# openSX70-dongle-USB-V2-1.net
KiCad netlist of a schematic drawn in EAGLE
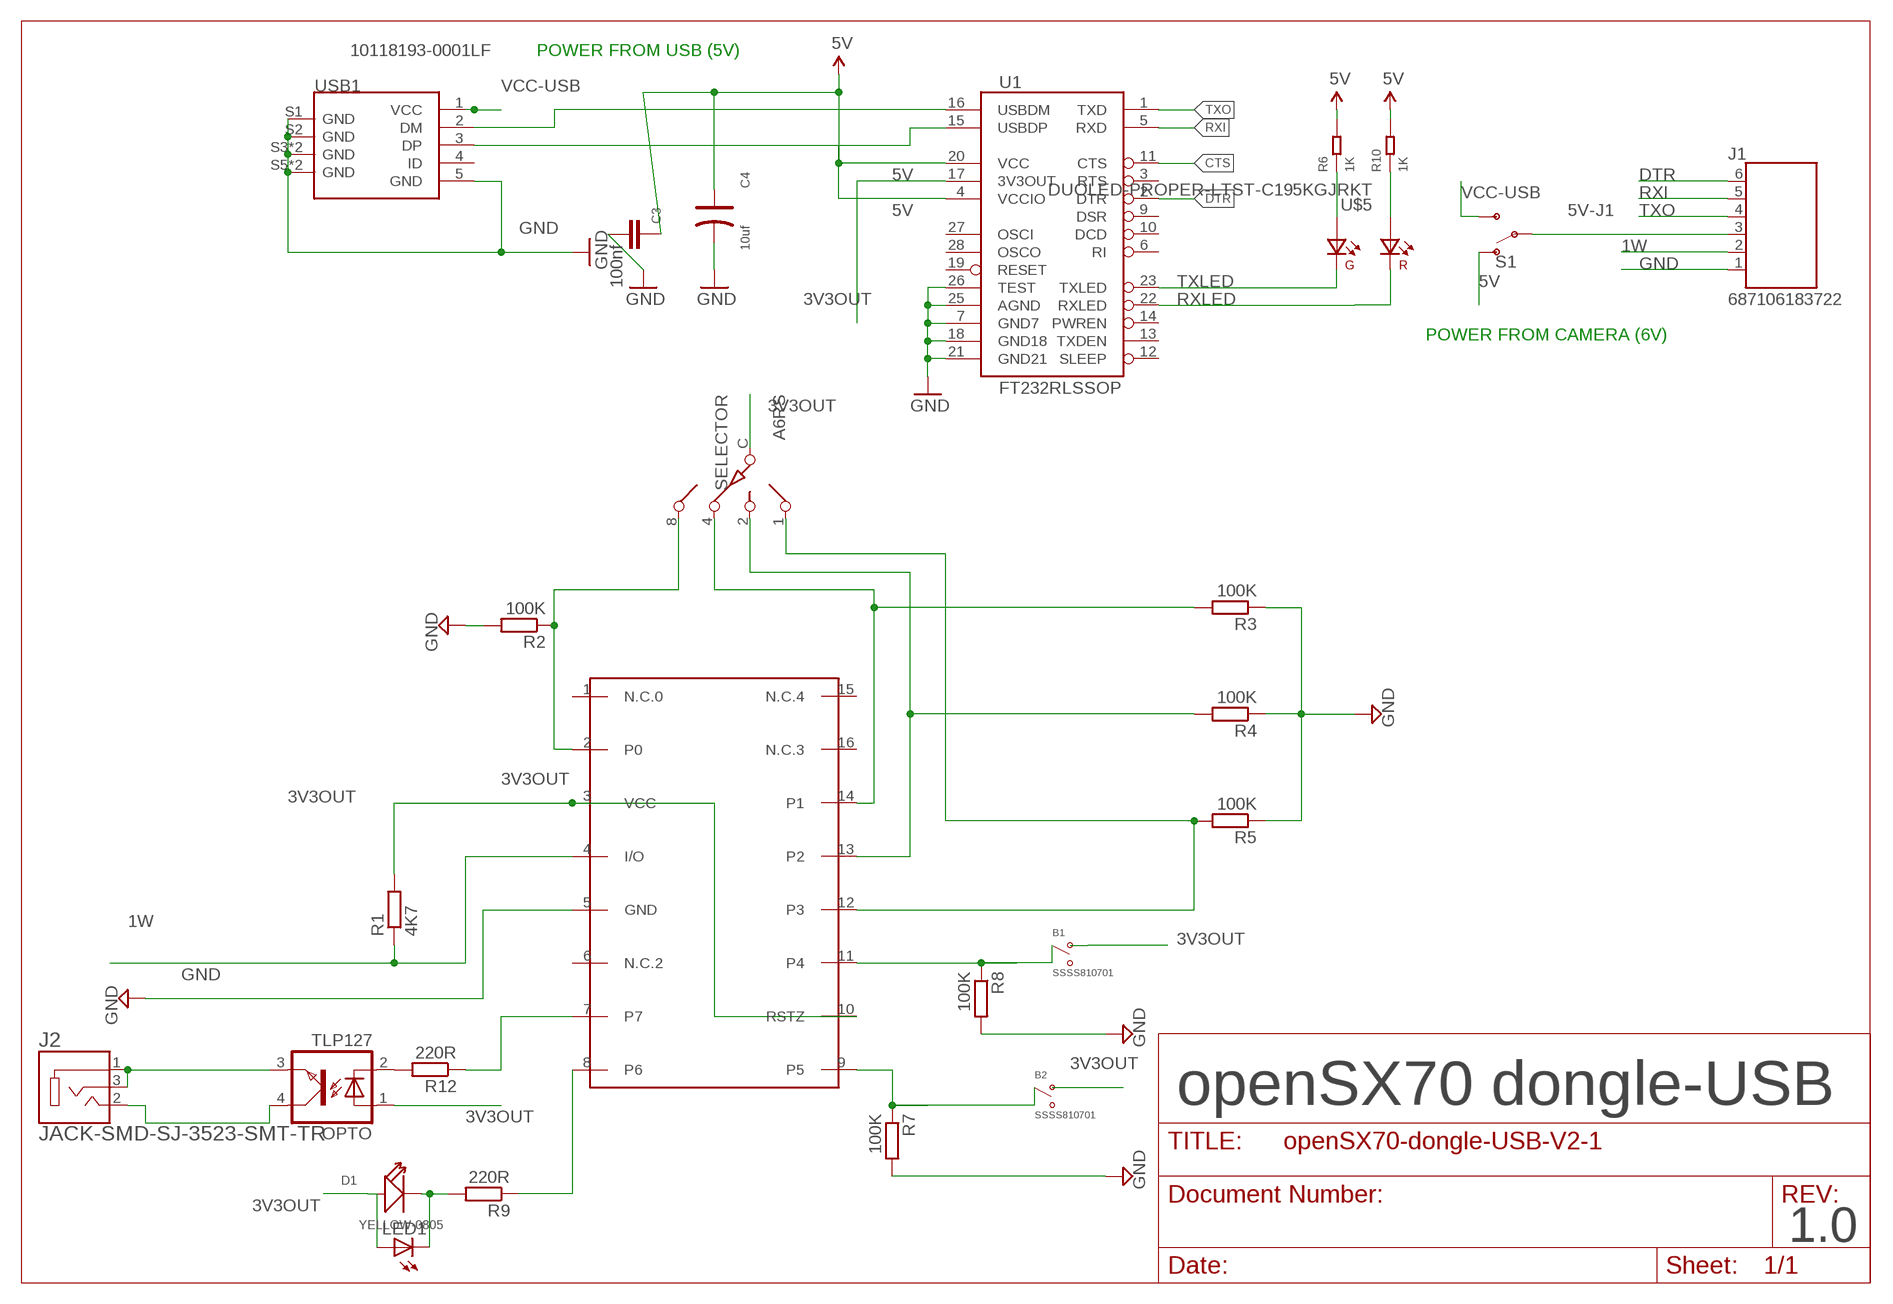
[diagram p0: schematic, sheet 1]

(export (version "E")
  (design (tool "Eeschema 10.0.6"))
  (components
    (comp (ref "B1")
      (value "SSSS810701")
      (footprint "eagle-import:SSSS810701")
      (fields (field (name "MF") "ALPS"))
      (libsource (lib "eagle-import") (part "SSSS810701"))
    )
    (comp (ref "B2")
      (value "SSSS810701")
      (footprint "eagle-import:SSSS810701")
      (fields (field (name "MF") "ALPS"))
      (libsource (lib "eagle-import") (part "SSSS810701"))
    )
    (comp (ref "C3")
      (value "100nf")
      (footprint "eagle-import:C0603")
      (libsource (lib "eagle-import") (part "C-EUC0603"))
    )
    (comp (ref "C4")
      (value "10uf")
      (footprint "eagle-import:AVX-A")
      (fields (field (name "MPN") "TAJA106K016RNJ"))
      (libsource (lib "eagle-import") (part "TANTALUM-SMD-10UF-16V-10%(AVX-A)"))
    )
    (comp (ref "D1")
      (value "YELLOW-0805")
      (footprint "eagle-import:LED-0805")
      (fields (field (name "MPN") "17-215UYC/S530-A3/TR8"))
      (libsource (lib "eagle-import") (part "SMD-LED-CLEAR-YELLOW(0805)"))
    )
    (comp (ref "DS2408")
      (value "DS2408")
      (footprint "eagle-import:SO16")
      (libsource (lib "eagle-import") (part "DS2408"))
    )
    (comp (ref "J1")
      (value "687106183722")
      (footprint "eagle-import:687106183722")
      (fields (field (name "MF") "Wurth Electronics"))
      (libsource (lib "eagle-import") (part "687106183722"))
    )
    (comp (ref "J2")
      (value "JACK-SMD-SJ-3523-SMT-TR")
      (footprint "eagle-import:CUI_SJ-3523-SMT-TR")
      (fields (field (name "MF") "CUI Inc.") (field (name "MP") "SJ-3523-SMT-TR"))
      (libsource (lib "eagle-import") (part "JACK-SMD-SJ-3523-SMT-TR"))
    )
    (comp (ref "LED1")
      (value "LED3MM")
      (footprint "eagle-import:LED3MM")
      (libsource (lib "eagle-import") (part "LED3MM"))
    )
    (comp (ref "OPTO")
      (value "TLP127")
      (footprint "eagle-import:SO-4")
      (libsource (lib "eagle-import") (part "TLP127"))
    )
    (comp (ref "R1")
      (value "4K7")
      (footprint "eagle-import:R0603")
      (libsource (lib "eagle-import") (part "R-EU_R0603"))
    )
    (comp (ref "R2")
      (value "100K")
      (footprint "eagle-import:R0603")
      (libsource (lib "eagle-import") (part "R-EU_R0603"))
    )
    (comp (ref "R3")
      (value "100K")
      (footprint "eagle-import:R0603")
      (libsource (lib "eagle-import") (part "R-EU_R0603"))
    )
    (comp (ref "R4")
      (value "100K")
      (footprint "eagle-import:R0603")
      (libsource (lib "eagle-import") (part "R-EU_R0603"))
    )
    (comp (ref "R5")
      (value "100K")
      (footprint "eagle-import:R0603")
      (libsource (lib "eagle-import") (part "R-EU_R0603"))
    )
    (comp (ref "R6")
      (value "1K")
      (footprint "eagle-import:R0603")
      (fields (field (name "MPN") "RC0603FR-071KL"))
      (libsource (lib "eagle-import") (part "SMD-RES-1K-1%-1/10W(0603)"))
    )
    (comp (ref "R7")
      (value "100K")
      (footprint "eagle-import:R0603")
      (libsource (lib "eagle-import") (part "R-EU_R0603"))
    )
    (comp (ref "R8")
      (value "100K")
      (footprint "eagle-import:R0603")
      (libsource (lib "eagle-import") (part "R-EU_R0603"))
    )
    (comp (ref "R9")
      (value "220R")
      (footprint "eagle-import:R0603")
      (libsource (lib "eagle-import") (part "R-EU_R0603"))
    )
    (comp (ref "R10")
      (value "1K")
      (footprint "eagle-import:R0603")
      (fields (field (name "MPN") "RC0603FR-071KL"))
      (libsource (lib "eagle-import") (part "SMD-RES-1K-1%-1/10W(0603)"))
    )
    (comp (ref "R12")
      (value "220R")
      (footprint "eagle-import:R0603")
      (libsource (lib "eagle-import") (part "R-EU_R0603"))
    )
    (comp (ref "S1")
      (value "SWITCH-SPDT-SMD-RIGHT-ANGLE")
      (footprint "eagle-import:SWITCH_SPST_SMD_A")
      (libsource (lib "eagle-import") (part "SWITCH-SPDT-SMD-RIGHT-ANGLE"))
    )
    (comp (ref "SELECTOR")
      (value "A6RS")
      (footprint "eagle-import:A6RS-161RS")
      (libsource (lib "eagle-import") (part "A6RS"))
    )
    (comp (ref "U$5")
      (value "DUOLED-PROPER-LTST-C195KGJRKT")
      (footprint "eagle-import:LTST-BILED-15X16")
      (fields (field (name "MF") "Lite-On Inc.") (field (name "MP") "LTST-C195KGJRKT"))
      (libsource (lib "eagle-import") (part "DUOLED-PROPER-LTST-C195KGJRKT"))
    )
    (comp (ref "U1")
      (value "FT232RLSSOP")
      (footprint "eagle-import:SSOP28DB")
      (libsource (lib "eagle-import") (part "FT232RLSSOP"))
    )
    (comp (ref "USB1")
      (value "10118193-0001LF")
      (footprint "eagle-import:MICRO-USB5+6P-SMD-0.65-B")
      (libsource (lib "eagle-import") (part "MICRO-USB-SMD-B-(10118193-0001LF)"))
    )
  )
  (nets
    (net (code "1") (name "/1W") (class "Default")
      (node (ref "DS2408") (pin "4") (pinfunction "I/O_4") (pintype "bidirectional"))
      (node (ref "J1") (pin "2") (pinfunction "5_2") (pintype "passive"))
      (node (ref "R1") (pin "1") (pinfunction "1_1") (pintype "passive"))
    )
    (net (code "2") (name "/3V3OUT") (class "Default")
      (node (ref "B1") (pin "3") (pinfunction "A_3") (pintype "bidirectional"))
      (node (ref "B2") (pin "3") (pinfunction "A_3") (pintype "bidirectional"))
      (node (ref "D1") (pin "+") (pinfunction "+_+") (pintype "passive"))
      (node (ref "DS2408") (pin "10") (pinfunction "RSTZ_10") (pintype "bidirectional"))
      (node (ref "DS2408") (pin "3") (pinfunction "VCC_3") (pintype "bidirectional"))
      (node (ref "LED1") (pin "A") (pinfunction "A_A") (pintype "passive"))
      (node (ref "OPTO") (pin "1") (pinfunction "A_1") (pintype "passive"))
      (node (ref "R1") (pin "2") (pinfunction "2_2") (pintype "passive"))
      (node (ref "SELECTOR") (pin "C") (pinfunction "C_C") (pintype "passive"))
      (node (ref "U1") (pin "17") (pinfunction "3V3OUT_17") (pintype "output"))
    )
    (net (code "3") (name "/5V-J1") (class "Default")
      (node (ref "J1") (pin "3") (pinfunction "4_3") (pintype "passive"))
      (node (ref "S1") (pin "2") (pinfunction "P_2") (pintype "passive"))
    )
    (net (code "4") (name "/RXLED") (class "Default")
      (node (ref "U$5") (pin "P$4") (pinfunction "K2_P$4") (pintype "passive"))
      (node (ref "U1") (pin "22") (pinfunction "RXLED_22") (pintype "input"))
    )
    (net (code "5") (name "/TXLED") (class "Default")
      (node (ref "U$5") (pin "P$3") (pinfunction "K1_P$3") (pintype "passive"))
      (node (ref "U1") (pin "23") (pinfunction "TXLED_23") (pintype "input"))
    )
    (net (code "6") (name "/VCC-USB") (class "Default")
      (node (ref "S1") (pin "3") (pinfunction "S_3") (pintype "passive"))
      (node (ref "USB1") (pin "1") (pinfunction "VCC_1") (pintype "bidirectional"))
    )
    (net (code "7") (name "5V") (class "Default")
      (node (ref "C3") (pin "1") (pinfunction "1_1") (pintype "passive"))
      (node (ref "C4") (pin "+") (pinfunction "+_+") (pintype "passive"))
      (node (ref "R10") (pin "2") (pinfunction "2_2") (pintype "passive"))
      (node (ref "R6") (pin "2") (pinfunction "2_2") (pintype "passive"))
      (node (ref "S1") (pin "1") (pinfunction "O_1") (pintype "passive"))
      (node (ref "U1") (pin "20") (pinfunction "VCC_20") (pintype "power_in"))
      (node (ref "U1") (pin "4") (pinfunction "VCCIO_4") (pintype "power_in"))
    )
    (net (code "8") (name "CTS") (class "Default")
      (node (ref "U1") (pin "11") (pinfunction "CTS_11") (pintype "input"))
    )
    (net (code "9") (name "DTR") (class "Default")
      (node (ref "J1") (pin "6") (pinfunction "1_6") (pintype "passive"))
      (node (ref "U1") (pin "2") (pinfunction "DTR_2") (pintype "output"))
    )
    (net (code "10") (name "GND") (class "Default")
      (node (ref "C3") (pin "2") (pinfunction "2_2") (pintype "passive"))
      (node (ref "C4") (pin "-") (pinfunction "-_-") (pintype "passive"))
      (node (ref "DS2408") (pin "5") (pinfunction "GND_5") (pintype "bidirectional"))
      (node (ref "J1") (pin "1") (pinfunction "6_1") (pintype "passive"))
      (node (ref "R2") (pin "2") (pinfunction "2_2") (pintype "passive"))
      (node (ref "R3") (pin "1") (pinfunction "1_1") (pintype "passive"))
      (node (ref "R4") (pin "1") (pinfunction "1_1") (pintype "passive"))
      (node (ref "R5") (pin "1") (pinfunction "1_1") (pintype "passive"))
      (node (ref "R7") (pin "2") (pinfunction "2_2") (pintype "passive"))
      (node (ref "R8") (pin "2") (pinfunction "2_2") (pintype "passive"))
      (node (ref "U1") (pin "18") (pinfunction "GND18_18") (pintype "power_in"))
      (node (ref "U1") (pin "21") (pinfunction "GND21_21") (pintype "power_in"))
      (node (ref "U1") (pin "25") (pinfunction "AGND_25") (pintype "power_in"))
      (node (ref "U1") (pin "26") (pinfunction "TEST_26") (pintype "input"))
      (node (ref "U1") (pin "7") (pinfunction "GND7_7") (pintype "power_in"))
      (node (ref "USB1") (pin "5") (pinfunction "GND_5") (pintype "bidirectional"))
      (node (ref "USB1") (pin "S1") (pinfunction "GND_S1") (pintype "bidirectional"))
      (node (ref "USB1") (pin "S2") (pinfunction "GND_S2") (pintype "bidirectional"))
      (node (ref "USB1") (pin "S3") (pinfunction "GND_S3") (pintype "bidirectional"))
      (node (ref "USB1") (pin "S4") (pinfunction "GND_S4") (pintype "bidirectional"))
      (node (ref "USB1") (pin "S5") (pinfunction "GND_S5") (pintype "bidirectional"))
      (node (ref "USB1") (pin "S6") (pinfunction "GND_S6") (pintype "bidirectional"))
    )
    (net (code "11") (name "Net-(B1-COM)") (class "Default")
      (node (ref "B1") (pin "2") (pinfunction "COM_2") (pintype "bidirectional"))
      (node (ref "DS2408") (pin "11") (pinfunction "P4_11") (pintype "bidirectional"))
      (node (ref "R8") (pin "1") (pinfunction "1_1") (pintype "passive"))
    )
    (net (code "12") (name "Net-(B2-COM)") (class "Default")
      (node (ref "B2") (pin "2") (pinfunction "COM_2") (pintype "bidirectional"))
      (node (ref "DS2408") (pin "9") (pinfunction "P5_9") (pintype "bidirectional"))
      (node (ref "R7") (pin "1") (pinfunction "1_1") (pintype "passive"))
    )
    (net (code "13") (name "Net-(DS2408-P0)") (class "Default")
      (node (ref "DS2408") (pin "2") (pinfunction "P0_2") (pintype "bidirectional"))
      (node (ref "R2") (pin "1") (pinfunction "1_1") (pintype "passive"))
      (node (ref "SELECTOR") (pin "8") (pinfunction "8_8") (pintype "passive"))
    )
    (net (code "14") (name "Net-(DS2408-P1)") (class "Default")
      (node (ref "DS2408") (pin "14") (pinfunction "P1_14") (pintype "bidirectional"))
      (node (ref "R3") (pin "2") (pinfunction "2_2") (pintype "passive"))
      (node (ref "SELECTOR") (pin "4") (pinfunction "4_4") (pintype "passive"))
    )
    (net (code "15") (name "Net-(DS2408-P2)") (class "Default")
      (node (ref "DS2408") (pin "13") (pinfunction "P2_13") (pintype "bidirectional"))
      (node (ref "R4") (pin "2") (pinfunction "2_2") (pintype "passive"))
      (node (ref "SELECTOR") (pin "2") (pinfunction "2_2") (pintype "passive"))
    )
    (net (code "16") (name "Net-(DS2408-P3)") (class "Default")
      (node (ref "DS2408") (pin "12") (pinfunction "P3_12") (pintype "bidirectional"))
      (node (ref "R5") (pin "2") (pinfunction "2_2") (pintype "passive"))
      (node (ref "SELECTOR") (pin "1") (pinfunction "1_1") (pintype "passive"))
    )
    (net (code "17") (name "Net-(DS2408-P6)") (class "Default")
      (node (ref "DS2408") (pin "8") (pinfunction "P6_8") (pintype "bidirectional"))
      (node (ref "R9") (pin "1") (pinfunction "1_1") (pintype "passive"))
    )
    (net (code "18") (name "Net-(DS2408-P7)") (class "Default")
      (node (ref "DS2408") (pin "7") (pinfunction "P7_7") (pintype "bidirectional"))
      (node (ref "R12") (pin "1") (pinfunction "1_1") (pintype "passive"))
    )
    (net (code "19") (name "Net-(LED1-C)") (class "Default")
      (node (ref "D1") (pin "-") (pinfunction "-_-") (pintype "passive"))
      (node (ref "LED1") (pin "K") (pinfunction "C_K") (pintype "passive"))
      (node (ref "R9") (pin "2") (pinfunction "2_2") (pintype "passive"))
    )
    (net (code "20") (name "Net-(OPTO-C)") (class "Default")
      (node (ref "OPTO") (pin "2") (pinfunction "C_2") (pintype "passive"))
      (node (ref "R12") (pin "2") (pinfunction "2_2") (pintype "passive"))
    )
    (net (code "21") (name "Net-(OPTO-COL)") (class "Default")
      (node (ref "J2") (pin "2") (pinfunction "2_2") (pintype "passive"))
      (node (ref "OPTO") (pin "4") (pinfunction "COL_4") (pintype "passive"))
    )
    (net (code "22") (name "Net-(OPTO-EMIT)") (class "Default")
      (node (ref "J2") (pin "1") (pinfunction "1_1") (pintype "passive"))
      (node (ref "J2") (pin "3") (pinfunction "3_3") (pintype "passive"))
      (node (ref "OPTO") (pin "3") (pinfunction "EMIT_3") (pintype "passive"))
    )
    (net (code "23") (name "Net-(U$5-A1)") (class "Default")
      (node (ref "R6") (pin "1") (pinfunction "1_1") (pintype "passive"))
      (node (ref "U$5") (pin "P$1") (pinfunction "A1_P$1") (pintype "passive"))
    )
    (net (code "24") (name "Net-(U$5-A2)") (class "Default")
      (node (ref "R10") (pin "1") (pinfunction "1_1") (pintype "passive"))
      (node (ref "U$5") (pin "P$2") (pinfunction "A2_P$2") (pintype "passive"))
    )
    (net (code "25") (name "Net-(U1-USBDM)") (class "Default")
      (node (ref "U1") (pin "16") (pinfunction "USBDM_16") (pintype "bidirectional"))
      (node (ref "USB1") (pin "2") (pinfunction "DM_2") (pintype "bidirectional"))
    )
    (net (code "26") (name "Net-(U1-USBDP)") (class "Default")
      (node (ref "U1") (pin "15") (pinfunction "USBDP_15") (pintype "bidirectional"))
      (node (ref "USB1") (pin "3") (pinfunction "DP_3") (pintype "bidirectional"))
    )
    (net (code "27") (name "RXI") (class "Default")
      (node (ref "J1") (pin "5") (pinfunction "2_5") (pintype "passive"))
      (node (ref "U1") (pin "5") (pinfunction "RXD_5") (pintype "input"))
    )
    (net (code "28") (name "TXO") (class "Default")
      (node (ref "J1") (pin "4") (pinfunction "3_4") (pintype "passive"))
      (node (ref "U1") (pin "1") (pinfunction "TXD_1") (pintype "output"))
    )
    (net (code "29") (name "unconnected-(B1-B-Pad1)") (class "Default")
      (node (ref "B1") (pin "1") (pinfunction "B_1") (pintype "bidirectional"))
    )
    (net (code "30") (name "unconnected-(B2-B-Pad1)") (class "Default")
      (node (ref "B2") (pin "1") (pinfunction "B_1") (pintype "bidirectional"))
    )
    (net (code "31") (name "unconnected-(DS2408-N.C.0-Pad1)") (class "Default")
      (node (ref "DS2408") (pin "1") (pinfunction "N.C.0_1") (pintype "bidirectional"))
    )
    (net (code "32") (name "unconnected-(DS2408-N.C.2-Pad6)") (class "Default")
      (node (ref "DS2408") (pin "6") (pinfunction "N.C.2_6") (pintype "bidirectional"))
    )
    (net (code "33") (name "unconnected-(DS2408-N.C.3-Pad16)") (class "Default")
      (node (ref "DS2408") (pin "16") (pinfunction "N.C.3_16") (pintype "bidirectional"))
    )
    (net (code "34") (name "unconnected-(DS2408-N.C.4-Pad15)") (class "Default")
      (node (ref "DS2408") (pin "15") (pinfunction "N.C.4_15") (pintype "bidirectional"))
    )
    (net (code "35") (name "unconnected-(U1-DCD-Pad10)") (class "Default")
      (node (ref "U1") (pin "10") (pinfunction "DCD_10") (pintype "input"))
    )
    (net (code "36") (name "unconnected-(U1-DSR-Pad9)") (class "Default")
      (node (ref "U1") (pin "9") (pinfunction "DSR_9") (pintype "input"))
    )
    (net (code "37") (name "unconnected-(U1-OSCI-Pad27)") (class "Default")
      (node (ref "U1") (pin "27") (pinfunction "OSCI_27") (pintype "input"))
    )
    (net (code "38") (name "unconnected-(U1-OSCO-Pad28)") (class "Default")
      (node (ref "U1") (pin "28") (pinfunction "OSCO_28") (pintype "output"))
    )
    (net (code "39") (name "unconnected-(U1-PWREN-Pad14)") (class "Default")
      (node (ref "U1") (pin "14") (pinfunction "PWREN_14") (pintype "input"))
    )
    (net (code "40") (name "unconnected-(U1-RESET-Pad19)") (class "Default")
      (node (ref "U1") (pin "19") (pinfunction "RESET_19") (pintype "input"))
    )
    (net (code "41") (name "unconnected-(U1-RI-Pad6)") (class "Default")
      (node (ref "U1") (pin "6") (pinfunction "RI_6") (pintype "input"))
    )
    (net (code "42") (name "unconnected-(U1-RTS-Pad3)") (class "Default")
      (node (ref "U1") (pin "3") (pinfunction "RTS_3") (pintype "output"))
    )
    (net (code "43") (name "unconnected-(U1-SLEEP-Pad12)") (class "Default")
      (node (ref "U1") (pin "12") (pinfunction "SLEEP_12") (pintype "input"))
    )
    (net (code "44") (name "unconnected-(U1-TXDEN-Pad13)") (class "Default")
      (node (ref "U1") (pin "13") (pinfunction "TXDEN_13") (pintype "input"))
    )
    (net (code "45") (name "unconnected-(USB1-ID-Pad4)") (class "Default")
      (node (ref "USB1") (pin "4") (pinfunction "ID_4") (pintype "bidirectional"))
    )
  )
)
